# Temperature_sensing_and_heater_power.net
KiCad netlist of a schematic drawn in Altium Designer
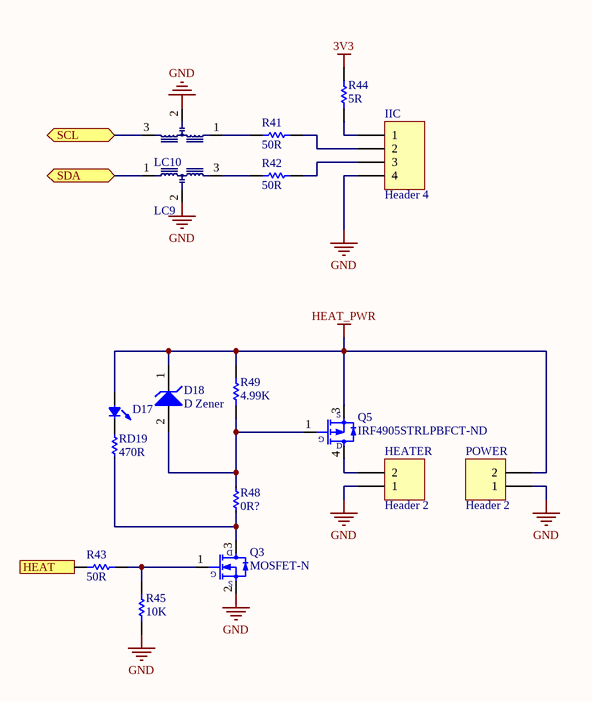
[diagram p0: Temperature sensing and heater power.SchDoc]

(export (version "E")
  (design (tool "Eeschema 10.0.6"))
  (components
    (comp (ref "D17")
      (value "LED0")
      (footprint "0603 SMT LED")
      (description "T 1 3/4 LED")
      (fields (field (name "PUBLISHER") "Altium Limited"))
      (libsource (lib "Miscellaneous Devices") (part "LED0"))
    )
    (comp (ref "D18")
      (value "D Zener")
      (footprint "SOD123/X.85")
      (description "Zener Diode")
      (fields (field (name "PUBLISHER") "Altium Limited"))
      (libsource (lib "Miscellaneous Devices") (part "D Zener"))
    )
    (comp (ref "HEATER")
      (value "Header 2")
      (footprint "Molex Mini-Fit Jr 5569 - 2 Pin, RA")
      (description "Header, 2-Pin")
      (fields (field (name "PUBLISHER") "Altium Limited"))
      (libsource (lib "Miscellaneous Connectors") (part "Header 2"))
    )
    (comp (ref "IIC")
      (value "Header 4")
      (footprint "AMPModu MTE 4 Pin Shrouded Header")
      (description "Header, 4-Pin")
      (fields (field (name "PUBLISHER") "Altium Limited"))
      (libsource (lib "Miscellaneous Connectors") (part "Header 4"))
    )
    (comp (ref "LC9")
      (value "MEM2012F")
      (footprint "MEM2012S LC Filter")
      (description "Signal Line 3-terminal Filters")
      (libsource (lib "Unsorted") (part "MEM2012F - Signal Filter"))
    )
    (comp (ref "LC10")
      (value "MEM2012F")
      (footprint "MEM2012S LC Filter")
      (description "Signal Line 3-terminal Filters")
      (libsource (lib "Unsorted") (part "MEM2012F - Signal Filter"))
    )
    (comp (ref "POWER")
      (value "Header 2")
      (footprint "Molex Mini-Fit Jr 5569 - 2 Pin, RA")
      (description "Header, 2-Pin")
      (fields (field (name "PUBLISHER") "Altium Limited"))
      (libsource (lib "") (part "Header 2_1"))
    )
    (comp (ref "Q3")
      (value "MOSFET-N")
      (footprint "SOT23-3N")
      (description "N-Channel MOSFET")
      (fields (field (name "PUBLISHER") "Altium Limited"))
      (libsource (lib "Miscellaneous Devices") (part "MOSFET-N"))
    )
    (comp (ref "Q5")
      (value "IRF4905STRLPBFCT-ND")
      (footprint "TO254P1520-3_4N")
      (description "P-Channel MOSFET")
      (fields (field (name "PUBLISHER") "Altium Limited"))
      (libsource (lib "Miscellaneous Devices") (part "MOSFET-P"))
    )
    (comp (ref "R41")
      (value "50R")
      (footprint "0603R")
      (description "Semiconductor Resistor")
      (fields (field (name "Comment") "Res Semi") (field (name "PUBLISHER") "Altium Limited"))
      (libsource (lib "Miscellaneous Devices") (part "Res Semi"))
    )
    (comp (ref "R42")
      (value "50R")
      (footprint "0603R")
      (description "Semiconductor Resistor")
      (fields (field (name "Comment") "Res Semi") (field (name "PUBLISHER") "Altium Limited"))
      (libsource (lib "Miscellaneous Devices") (part "Res Semi"))
    )
    (comp (ref "R43")
      (value "50R")
      (footprint "0603R")
      (description "Semiconductor Resistor")
      (fields (field (name "Comment") "Res Semi") (field (name "PUBLISHER") "Altium Limited"))
      (libsource (lib "Miscellaneous Devices") (part "Res Semi"))
    )
    (comp (ref "R44")
      (value "5R")
      (footprint "1206R")
      (description "Semiconductor Resistor")
      (fields (field (name "Comment") "Res Semi") (field (name "PUBLISHER") "Altium Limited"))
      (libsource (lib "Miscellaneous Devices") (part "Res Semi"))
    )
    (comp (ref "R45")
      (value "10K")
      (footprint "0603R")
      (description "Semiconductor Resistor")
      (fields (field (name "Comment") "Res Semi") (field (name "PUBLISHER") "Altium Limited"))
      (libsource (lib "Miscellaneous Devices") (part "Res Semi"))
    )
    (comp (ref "R48")
      (value "0R?")
      (footprint "0603R")
      (description "Semiconductor Resistor")
      (fields (field (name "Comment") "Res Semi Small") (field (name "PUBLISHER") "Altium Limited"))
      (libsource (lib "Miscellaneous Devices") (part "Res Semi Small"))
    )
    (comp (ref "R49")
      (value "4.99K")
      (footprint "1206R")
      (description "Semiconductor Resistor")
      (fields (field (name "Comment") "Res Semi") (field (name "PUBLISHER") "Altium Limited"))
      (libsource (lib "Miscellaneous Devices") (part "Res Semi"))
    )
    (comp (ref "RD19")
      (value "470R")
      (footprint "0603R")
      (description "Semiconductor Resistor")
      (fields (field (name "Comment") "Res Semi Small") (field (name "PUBLISHER") "Altium Limited"))
      (libsource (lib "Miscellaneous Devices") (part "Res Semi Small"))
    )
  )
  (nets
    (net (code "1") (name "/HEAT") (class "Default")
      (node (ref "R43") (pin "1") (pinfunction "1_1") (pintype "passive"))
    )
    (net (code "2") (name "/SCL") (class "Default")
      (node (ref "LC10") (pin "3") (pinfunction "3_3") (pintype "passive"))
    )
    (net (code "3") (name "/SDA") (class "Default")
      (node (ref "LC9") (pin "1") (pinfunction "1_1") (pintype "passive"))
    )
    (net (code "4") (name "3V3") (class "Default")
      (node (ref "R44") (pin "2") (pinfunction "2_2") (pintype "passive"))
    )
    (net (code "5") (name "GND") (class "Default")
      (node (ref "HEATER") (pin "1") (pinfunction "1_1") (pintype "passive"))
      (node (ref "IIC") (pin "4") (pinfunction "4_4") (pintype "passive"))
      (node (ref "LC10") (pin "2") (pinfunction "2_2") (pintype "passive"))
      (node (ref "LC9") (pin "2") (pinfunction "2_2") (pintype "passive"))
      (node (ref "POWER") (pin "1") (pinfunction "1_1") (pintype "passive"))
      (node (ref "Q3") (pin "2") (pinfunction "S_2") (pintype "passive"))
      (node (ref "R45") (pin "1") (pinfunction "1_1") (pintype "passive"))
    )
    (net (code "6") (name "HEAT_PWR") (class "Default")
      (node (ref "D17") (pin "1") (pinfunction "1_1") (pintype "passive"))
      (node (ref "D18") (pin "1") (pinfunction "A_1") (pintype "passive"))
      (node (ref "POWER") (pin "2") (pinfunction "2_2") (pintype "passive"))
      (node (ref "Q5") (pin "3") (pinfunction "D_3") (pintype "passive"))
      (node (ref "R49") (pin "2") (pinfunction "2_2") (pintype "passive"))
    )
    (net (code "7") (name "Net-(D17-Pad2)") (class "Default")
      (node (ref "D17") (pin "2") (pinfunction "2_2") (pintype "passive"))
      (node (ref "RD19") (pin "1") (pinfunction "1_1") (pintype "passive"))
    )
    (net (code "8") (name "Net-(D18-K)") (class "Default")
      (node (ref "D18") (pin "2") (pinfunction "K_2") (pintype "passive"))
      (node (ref "Q5") (pin "1") (pinfunction "G_1") (pintype "passive"))
      (node (ref "R48") (pin "1") (pinfunction "1_1") (pintype "passive"))
      (node (ref "R49") (pin "1") (pinfunction "1_1") (pintype "passive"))
    )
    (net (code "9") (name "Net-(IIC-Pad1)") (class "Default")
      (node (ref "IIC") (pin "1") (pinfunction "1_1") (pintype "passive"))
      (node (ref "R44") (pin "1") (pinfunction "1_1") (pintype "passive"))
    )
    (net (code "10") (name "Net-(IIC-Pad2)") (class "Default")
      (node (ref "IIC") (pin "2") (pinfunction "2_2") (pintype "passive"))
      (node (ref "R41") (pin "2") (pinfunction "2_2") (pintype "passive"))
    )
    (net (code "11") (name "Net-(IIC-Pad3)") (class "Default")
      (node (ref "IIC") (pin "3") (pinfunction "3_3") (pintype "passive"))
      (node (ref "R42") (pin "2") (pinfunction "2_2") (pintype "passive"))
    )
    (net (code "12") (name "Net-(LC9-Pad3)") (class "Default")
      (node (ref "LC9") (pin "3") (pinfunction "3_3") (pintype "passive"))
      (node (ref "R42") (pin "1") (pinfunction "1_1") (pintype "passive"))
    )
    (net (code "13") (name "Net-(LC10-Pad1)") (class "Default")
      (node (ref "LC10") (pin "1") (pinfunction "1_1") (pintype "passive"))
      (node (ref "R41") (pin "1") (pinfunction "1_1") (pintype "passive"))
    )
    (net (code "14") (name "Net-(Q3-D)") (class "Default")
      (node (ref "Q3") (pin "3") (pinfunction "D_3") (pintype "passive"))
      (node (ref "R48") (pin "2") (pinfunction "2_2") (pintype "passive"))
      (node (ref "RD19") (pin "2") (pinfunction "2_2") (pintype "passive"))
    )
    (net (code "15") (name "Net-(Q3-G)") (class "Default")
      (node (ref "Q3") (pin "1") (pinfunction "G_1") (pintype "passive"))
      (node (ref "R43") (pin "2") (pinfunction "2_2") (pintype "passive"))
      (node (ref "R45") (pin "2") (pinfunction "2_2") (pintype "passive"))
    )
    (net (code "16") (name "Net-(Q5-S)") (class "Default")
      (node (ref "HEATER") (pin "2") (pinfunction "2_2") (pintype "passive"))
      (node (ref "Q5") (pin "4") (pinfunction "S_4") (pintype "passive"))
    )
  )
)
